# 5_STM32KIT_Peripheral.net
KiCad netlist of a schematic drawn in Altium Designer
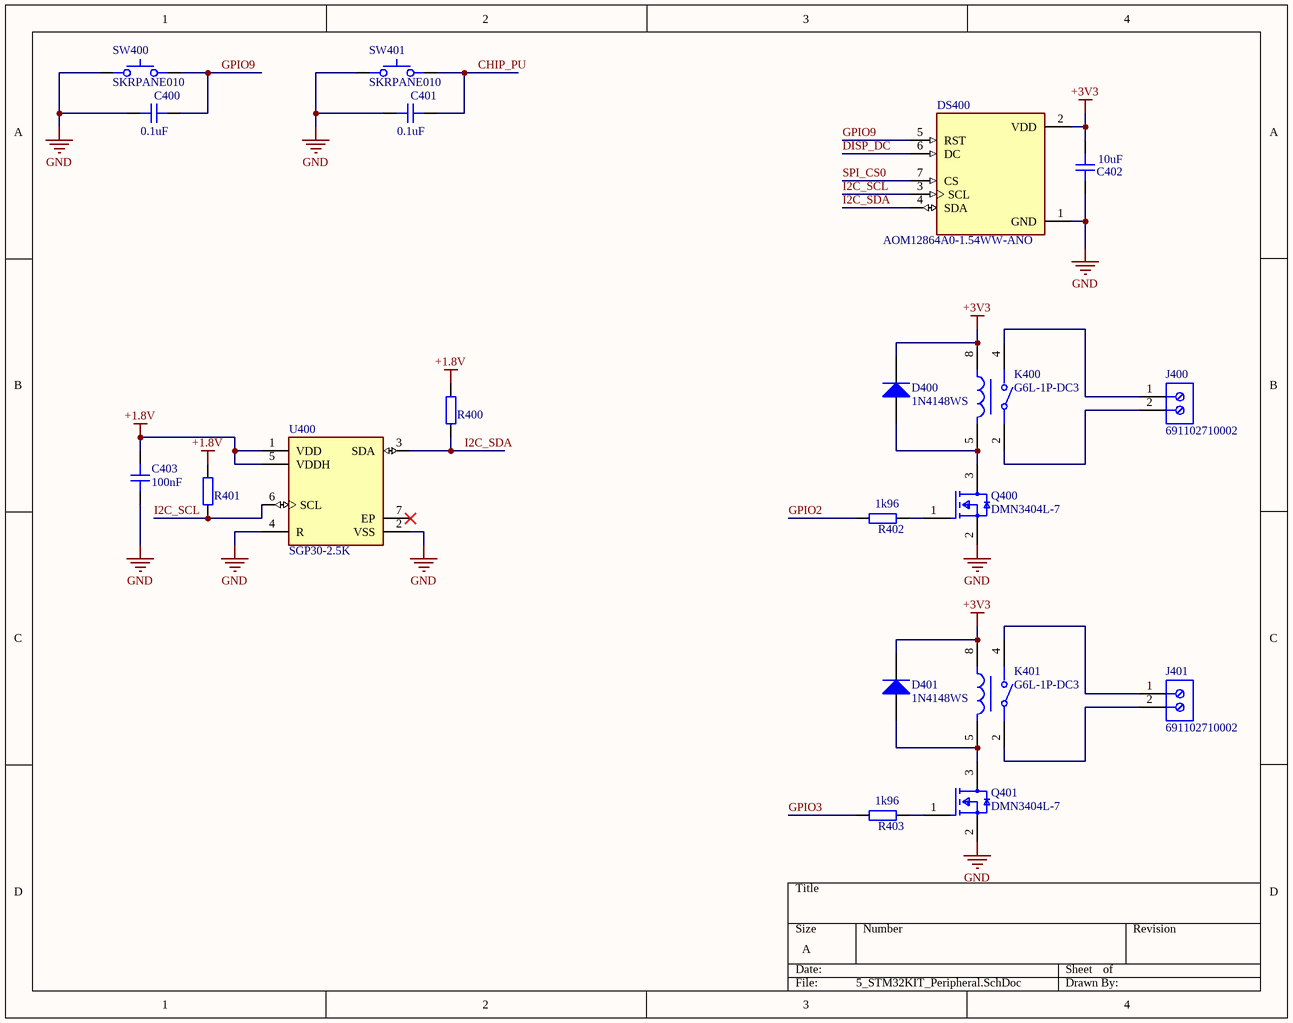
[diagram p0: 5_STM32KIT_Peripheral.SchDoc]

(export (version "E")
  (design (tool "Eeschema 10.0.6"))
  (components
    (comp (ref "C400")
      (value "0.1uF")
      (footprint "CAP_0402")
      (description "Capacitor SMD 0402")
      (fields (field (name "SOURCE") "Schematic-Lib-PhilsLab.SchLib"))
      (libsource (lib "Industrial University of Ho Chi Minh City") (part "CAP_EL_NP_5MM"))
    )
    (comp (ref "C401")
      (value "0.1uF")
      (footprint "CAP_0402")
      (description "Capacitor SMD 0402")
      (fields (field (name "SOURCE") "Schematic-Lib-PhilsLab.SchLib"))
      (libsource (lib "Industrial University of Ho Chi Minh City") (part "CAP_EL_NP_5MM"))
    )
    (comp (ref "C402")
      (value "10uF")
      (footprint "CAP_0402")
      (description "Capacitor SMD 0402")
      (fields (field (name "SOURCE") "Schematic-Lib-PhilsLab.SchLib"))
      (libsource (lib "Industrial University of Ho Chi Minh City") (part "CAP_EL_NP_5MM"))
    )
    (comp (ref "C403")
      (value "100nF")
      (footprint "CAP_0402")
      (description "Capacitor SMD 0402")
      (fields (field (name "SOURCE") "Schematic-Lib-PhilsLab.SchLib"))
      (libsource (lib "Industrial University of Ho Chi Minh City") (part "CAP_EL_NP_5MM"))
    )
    (comp (ref "D400")
      (value "1N4148WS")
      (footprint "FAIR-SOD-323_V")
      (description "Small Signal Diode, 75 V, 0.15 A, -55 to 150 degC, 2-Pin SOD-323, RoHS, Tape and Reel")
      (fields (field (name "MANUFACTURER") "Fairchild"))
      (libsource (lib "Industrial University of Ho Chi Minh City") (part "D-AK-2"))
    )
    (comp (ref "D401")
      (value "1N4148WS")
      (footprint "FAIR-SOD-323_V")
      (description "Small Signal Diode, 75 V, 0.15 A, -55 to 150 degC, 2-Pin SOD-323, RoHS, Tape and Reel")
      (fields (field (name "MANUFACTURER") "Fairchild"))
      (libsource (lib "Industrial University of Ho Chi Minh City") (part "D-AK-2"))
    )
    (comp (ref "DS400")
      (value "AOM12864A0-1.54WW-ANO")
      (footprint "LCD_AOM12864A0-1.54WW-ANO")
      (description "Non-Touch Graphic LCD Display Module - White OLED SPI 1.54 (39.12mm) 128 x 64")
      (fields (field (name "MF") "Orient Display"))
      (libsource (lib "Industrial University of Ho Chi Minh City") (part "AOM12864A0-1.54WW-ANO"))
    )
    (comp (ref "J400")
      (value "691102710002")
      (footprint "691102710002")
      (fields (field (name "VOLTAGE") "300V"))
      (libsource (lib "Altium Content Vault") (part "TBL - 1R - 02P - Screw"))
    )
    (comp (ref "J401")
      (value "691102710002")
      (footprint "691102710002")
      (fields (field (name "VOLTAGE") "300V"))
      (libsource (lib "Altium Content Vault") (part "TBL - 1R - 02P - Screw"))
    )
    (comp (ref "K400")
      (value "G6L-1P-DC3")
      (footprint "FP-G6L-1P-DC3-MFG")
      (description "RELAY TELECOM SPST 1A 3VDC")
      (libsource (lib "Altium Content Vault") (part "0b4cad2df39780911da7817dc4dbd4a"))
    )
    (comp (ref "K401")
      (value "G6L-1P-DC3")
      (footprint "FP-G6L-1P-DC3-MFG")
      (description "RELAY TELECOM SPST 1A 3VDC")
      (libsource (lib "Altium Content Vault") (part "0b4cad2df39780911da7817dc4dbd4a"))
    )
    (comp (ref "Q400")
      (value "DMN3404L-7")
      (footprint "FP-SOT23-MFG")
      (description "MOSFET N-CH 30V 5.8A SOT-23")
      (fields
        (field (name "OCTOPART") "https://octopart.com/dmn3404l-7-diodes+inc.-12409285")
        (field (name "MANUFACTURER") "Diodes Inc.")
      )
      (libsource (lib "Altium Content Vault") (part "0a9ea7c96deaaede766a5b531c28de0"))
    )
    (comp (ref "Q401")
      (value "DMN3404L-7")
      (footprint "FP-SOT23-MFG")
      (description "MOSFET N-CH 30V 5.8A SOT-23")
      (fields
        (field (name "OCTOPART") "https://octopart.com/dmn3404l-7-diodes+inc.-12409285")
        (field (name "MANUFACTURER") "Diodes Inc.")
      )
      (libsource (lib "Altium Content Vault") (part "0a9ea7c96deaaede766a5b531c28de0"))
    )
    (comp (ref "R400")
      (value "RES_0402")
      (footprint "RES_0402")
      (description "Resistor SMD 0402")
      (fields (field (name "SOURCE") "Schematic-Lib-PhilsLab.SchLib"))
      (libsource (lib "Industrial University of Ho Chi Minh City") (part "RES_5931"))
    )
    (comp (ref "R401")
      (value "RES_0402")
      (footprint "RES_0402")
      (description "Resistor SMD 0402")
      (fields (field (name "SOURCE") "Schematic-Lib-PhilsLab.SchLib"))
      (libsource (lib "Industrial University of Ho Chi Minh City") (part "RES_5931"))
    )
    (comp (ref "R402")
      (value "1k96")
      (footprint "RES_0402")
      (description "Resistor SMD 0402")
      (fields (field (name "SOURCE") "Schematic-Lib-PhilsLab.SchLib"))
      (libsource (lib "Industrial University of Ho Chi Minh City") (part "RES_5931"))
    )
    (comp (ref "R403")
      (value "1k96")
      (footprint "RES_0402")
      (description "Resistor SMD 0402")
      (fields (field (name "SOURCE") "Schematic-Lib-PhilsLab.SchLib"))
      (libsource (lib "Industrial University of Ho Chi Minh City") (part "RES_5931"))
    )
    (comp (ref "SW400")
      (value "SKRPANE010")
      (footprint "SKRPANE010")
      (description "Tactile Switch SMD SPST")
      (fields (field (name "MANUFACTURER") "Alps Alpine"))
      (libsource (lib "Schematic-Lib-PhilsLab") (part "SKRPANE010"))
    )
    (comp (ref "SW401")
      (value "SKRPANE010")
      (footprint "SKRPANE010")
      (description "Tactile Switch SMD SPST")
      (fields (field (name "MANUFACTURER") "Alps Alpine"))
      (libsource (lib "Schematic-Lib-PhilsLab") (part "SKRPANE010"))
    )
    (comp (ref "U400")
      (value "SGP30-2.5K")
      (footprint "FP-SGP30-2_5K-MFG")
      (description "AIR QUALITY GAS SENSOR FOR VOC'S")
      (fields
        (field (name "OCTOPART") "https://octopart.com/sgp30-2.5k-sensirion-84561789")
        (field (name "MANUFACTURER") "Sensirion")
      )
      (libsource (lib "Altium Content Vault") (part "83c16ec1942eefe8a5a6f6958230d5f"))
    )
  )
  (nets
    (net (code "1") (name "+1.8V") (class "Default")
      (node (ref "C403") (pin "2") (pinfunction "2_2") (pintype "passive"))
      (node (ref "R400") (pin "2") (pinfunction "2_2") (pintype "passive"))
      (node (ref "R401") (pin "2") (pinfunction "2_2") (pintype "passive"))
      (node (ref "U400") (pin "1") (pinfunction "VDD_1") (pintype "power_in"))
      (node (ref "U400") (pin "5") (pinfunction "VDDH_5") (pintype "power_in"))
    )
    (net (code "2") (name "+3V3") (class "Default")
      (node (ref "C402") (pin "2") (pinfunction "2_2") (pintype "passive"))
      (node (ref "D400") (pin "2") (pinfunction "K_2") (pintype "passive"))
      (node (ref "D401") (pin "2") (pinfunction "K_2") (pintype "passive"))
      (node (ref "DS400") (pin "2") (pinfunction "VDD_2") (pintype "power_in"))
      (node (ref "K400") (pin "8") (pinfunction "8_8") (pintype "passive"))
      (node (ref "K401") (pin "8") (pinfunction "8_8") (pintype "passive"))
    )
    (net (code "3") (name "/CHIP_PU") (class "Default")
      (node (ref "C401") (pin "2") (pinfunction "2_2") (pintype "passive"))
      (node (ref "SW401") (pin "12") (pintype "passive"))
    )
    (net (code "4") (name "/DISP_DC") (class "Default")
      (node (ref "DS400") (pin "6") (pinfunction "DC_6") (pintype "input"))
    )
    (net (code "5") (name "/GPIO2") (class "Default")
      (node (ref "R402") (pin "1") (pinfunction "1_1") (pintype "passive"))
    )
    (net (code "6") (name "/GPIO3") (class "Default")
      (node (ref "R403") (pin "1") (pinfunction "1_1") (pintype "passive"))
    )
    (net (code "7") (name "/GPIO9") (class "Default")
      (node (ref "C400") (pin "2") (pinfunction "2_2") (pintype "passive"))
      (node (ref "DS400") (pin "5") (pinfunction "RST_5") (pintype "input"))
      (node (ref "SW400") (pin "12") (pintype "passive"))
    )
    (net (code "8") (name "/I2C_SCL") (class "Default")
      (node (ref "DS400") (pin "3") (pinfunction "SCL_3") (pintype "input"))
      (node (ref "R401") (pin "1") (pinfunction "1_1") (pintype "passive"))
      (node (ref "U400") (pin "6") (pinfunction "SCL_6") (pintype "bidirectional"))
    )
    (net (code "9") (name "/I2C_SDA") (class "Default")
      (node (ref "DS400") (pin "4") (pinfunction "SDA_4") (pintype "bidirectional"))
      (node (ref "R400") (pin "1") (pinfunction "1_1") (pintype "passive"))
      (node (ref "U400") (pin "3") (pinfunction "SDA_3") (pintype "bidirectional"))
    )
    (net (code "10") (name "/SPI_CS0") (class "Default")
      (node (ref "DS400") (pin "7") (pinfunction "CS_7") (pintype "input"))
    )
    (net (code "11") (name "GND") (class "Default")
      (node (ref "C400") (pin "1") (pinfunction "1_1") (pintype "passive"))
      (node (ref "C401") (pin "1") (pinfunction "1_1") (pintype "passive"))
      (node (ref "C402") (pin "1") (pinfunction "1_1") (pintype "passive"))
      (node (ref "C403") (pin "1") (pinfunction "1_1") (pintype "passive"))
      (node (ref "DS400") (pin "1") (pinfunction "GND_1") (pintype "power_in"))
      (node (ref "Q400") (pin "2") (pinfunction "S_2") (pintype "passive"))
      (node (ref "Q401") (pin "2") (pinfunction "S_2") (pintype "passive"))
      (node (ref "SW400") (pin "34") (pintype "passive"))
      (node (ref "SW401") (pin "34") (pintype "passive"))
      (node (ref "U400") (pin "2") (pinfunction "VSS_2") (pintype "power_in"))
      (node (ref "U400") (pin "4") (pinfunction "R_4") (pintype "power_in"))
    )
    (net (code "12") (name "Net-(D400-A)") (class "Default")
      (node (ref "D400") (pin "1") (pinfunction "A_1") (pintype "passive"))
      (node (ref "K400") (pin "5") (pinfunction "5_5") (pintype "passive"))
      (node (ref "Q400") (pin "3") (pinfunction "D_3") (pintype "passive"))
    )
    (net (code "13") (name "Net-(D401-A)") (class "Default")
      (node (ref "D401") (pin "1") (pinfunction "A_1") (pintype "passive"))
      (node (ref "K401") (pin "5") (pinfunction "5_5") (pintype "passive"))
      (node (ref "Q401") (pin "3") (pinfunction "D_3") (pintype "passive"))
    )
    (net (code "14") (name "Net-(J400-Pad1)") (class "Default")
      (node (ref "J400") (pin "1") (pinfunction "1_1") (pintype "passive"))
      (node (ref "K400") (pin "4") (pinfunction "4_4") (pintype "passive"))
    )
    (net (code "15") (name "Net-(J400-Pad2)") (class "Default")
      (node (ref "J400") (pin "2") (pinfunction "2_2") (pintype "passive"))
      (node (ref "K400") (pin "2") (pinfunction "2_2") (pintype "passive"))
    )
    (net (code "16") (name "Net-(J401-Pad1)") (class "Default")
      (node (ref "J401") (pin "1") (pinfunction "1_1") (pintype "passive"))
      (node (ref "K401") (pin "4") (pinfunction "4_4") (pintype "passive"))
    )
    (net (code "17") (name "Net-(J401-Pad2)") (class "Default")
      (node (ref "J401") (pin "2") (pinfunction "2_2") (pintype "passive"))
      (node (ref "K401") (pin "2") (pinfunction "2_2") (pintype "passive"))
    )
    (net (code "18") (name "Net-(Q400-G)") (class "Default")
      (node (ref "Q400") (pin "1") (pinfunction "G_1") (pintype "passive"))
      (node (ref "R402") (pin "2") (pinfunction "2_2") (pintype "passive"))
    )
    (net (code "19") (name "Net-(Q401-G)") (class "Default")
      (node (ref "Q401") (pin "1") (pinfunction "G_1") (pintype "passive"))
      (node (ref "R403") (pin "2") (pinfunction "2_2") (pintype "passive"))
    )
    (net (code "20") (name "unconnected-(U400-EP-Pad7)") (class "Default")
      (node (ref "U400") (pin "7") (pinfunction "EP_7") (pintype "passive+no_connect"))
    )
  )
)
